# laugh_cry_gold.net
KiCad netlist of a schematic drawn in EAGLE
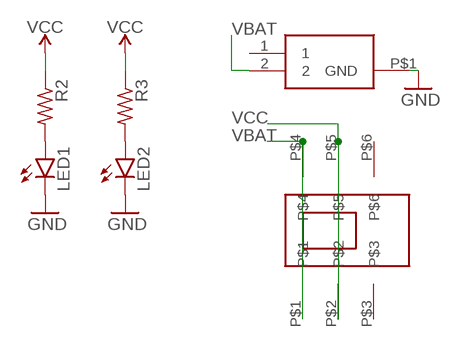
[diagram p0: schematic, sheet 1]

(export (version "E")
  (design (tool "Eeschema 10.0.6"))
  (components
    (comp (ref "LED1")
      (value "LEDCHIP-LED0805")
      (footprint "eagle-import:CHIP-LED0805")
      (libsource (lib "eagle-import") (part "LEDCHIP-LED0805"))
    )
    (comp (ref "LED2")
      (value "LEDCHIP-LED0805")
      (footprint "eagle-import:CHIP-LED0805")
      (libsource (lib "eagle-import") (part "LEDCHIP-LED0805"))
    )
    (comp (ref "R2")
      (value "R-US_R0603")
      (footprint "eagle-import:R0603")
      (libsource (lib "eagle-import") (part "R-US_R0603"))
    )
    (comp (ref "R3")
      (value "R-US_R0603")
      (footprint "eagle-import:R0603")
      (libsource (lib "eagle-import") (part "R-US_R0603"))
    )
    (comp (ref "U$1")
      (value "CL-SB-22A-02T-SLIDE-SWITCH-TUCKED-PADS")
      (footprint "eagle-import:CL-SB-22A-02T-DPDT-COMPACT-SWITCH")
      (libsource (lib "eagle-import") (part "CL-SB-22A-02T-SLIDE-SWITCH-TUCKED-PADS"))
    )
    (comp (ref "VBAT")
      (value "BAT-HLD-012-SMT")
      (footprint "eagle-import:BATHLD012SMT")
      (fields (field (name "MOUSER_PART_NUMBER") "712-BAT-HLD-012-SMT"))
      (libsource (lib "eagle-import") (part "BAT-HLD-012-SMT"))
    )
  )
  (nets
    (net (code "1") (name "/VBAT") (class "Default")
      (node (ref "U$1") (pin "P$1") (pinfunction "P$1_P$1") (pintype "bidirectional"))
      (node (ref "U$1") (pin "P$4") (pinfunction "P$4_P$4") (pintype "bidirectional"))
      (node (ref "VBAT") (pin "2") (pinfunction "2_2") (pintype "bidirectional"))
    )
    (net (code "2") (name "GND") (class "Default")
      (node (ref "LED1") (pin "C") (pinfunction "C_C") (pintype "passive"))
      (node (ref "LED2") (pin "C") (pinfunction "C_C") (pintype "passive"))
      (node (ref "VBAT") (pin "P$1") (pinfunction "GND_P$1") (pintype "bidirectional"))
    )
    (net (code "3") (name "Net-(LED1-PadA)") (class "Default")
      (node (ref "LED1") (pin "A") (pinfunction "A_A") (pintype "passive"))
      (node (ref "R2") (pin "2") (pinfunction "2_2") (pintype "passive"))
    )
    (net (code "4") (name "Net-(LED2-PadA)") (class "Default")
      (node (ref "LED2") (pin "A") (pinfunction "A_A") (pintype "passive"))
      (node (ref "R3") (pin "2") (pinfunction "2_2") (pintype "passive"))
    )
    (net (code "5") (name "VCC") (class "Default")
      (node (ref "R2") (pin "1") (pinfunction "1_1") (pintype "passive"))
      (node (ref "R3") (pin "1") (pinfunction "1_1") (pintype "passive"))
      (node (ref "U$1") (pin "P$2") (pinfunction "P$2_P$2") (pintype "bidirectional"))
      (node (ref "U$1") (pin "P$5") (pinfunction "P$5_P$5") (pintype "bidirectional"))
    )
    (net (code "6") (name "unconnected-(U$1-PadP$3)") (class "Default")
      (node (ref "U$1") (pin "P$3") (pinfunction "P$3_P$3") (pintype "bidirectional"))
    )
    (net (code "7") (name "unconnected-(U$1-PadP$6)") (class "Default")
      (node (ref "U$1") (pin "P$6") (pinfunction "P$6_P$6") (pintype "bidirectional"))
    )
    (net (code "8") (name "unconnected-(VBAT-Pad1)") (class "Default")
      (node (ref "VBAT") (pin "1") (pinfunction "1_1") (pintype "bidirectional"))
    )
  )
)
